# SPE_router_e-fuse_5A.net
KiCad netlist of a schematic drawn in Altium Designer
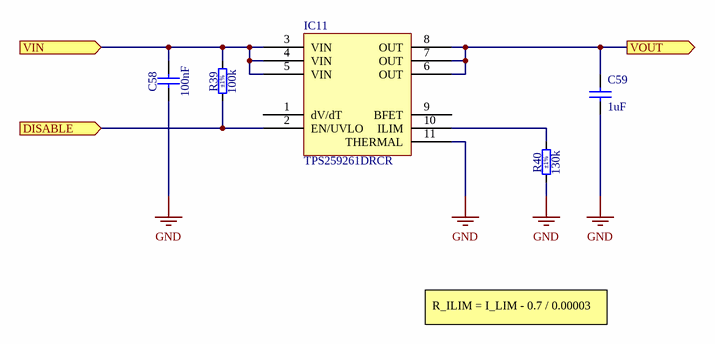
[diagram p0: SPE_router_e-fuse_5A.SchDoc]

(export (version "E")
  (design (tool "Eeschema 10.0.6"))
  (components
    (comp (ref "C58")
      (value "100nF")
      (footprint "CAPC1005X55N")
      (description "Non-polarised capacitor")
      (fields
        (field (name "PART NUMBER") "CC0402_100NF_16V_10%_X7R")
        (field (name "VOLTAGE") "16V")
        (field (name "AUTHOR") "CERN DEM JLC")
      )
      (libsource (lib "Capacitors") (part "Capacitor - non polarized"))
    )
    (comp (ref "C59")
      (value "1uF")
      (footprint "CAPC1005X55N")
      (description "Non-polarised capacitor")
      (fields
        (field (name "PART NUMBER") "CC0402_1UF_16V_10%_X5R")
        (field (name "VOLTAGE") "16V")
        (field (name "AUTHOR") "CERN DEM JLC")
      )
      (libsource (lib "Capacitors") (part "Capacitor - non polarized"))
    )
    (comp (ref "IC11")
      (value "TPS259261DRCR")
      (footprint "VSON50P300X100_HS-11N")
      (description "Hot Swap Controller 13.8V Positive Voltage 10-Pin VSON EP T/R")
      (fields (field (name "MANUFACTURER") "Texas Instruments"))
      (libsource (lib "SPE_router_lib") (part "TPS259261DRCR"))
    )
    (comp (ref "R39")
      (value "100k")
      (footprint "RESC1005X40N")
      (description "Resistor - 1%")
      (fields
        (field (name "TOLERANCE") "±1%")
        (field (name "PART NUMBER") "R0402_100K_1%_0.0625W_100PPM")
        (field (name "POWER") "0.0625W")
        (field (name "AUTHOR") "CERN DEM JLC")
      )
      (libsource (lib "Resistors") (part "Resistor - 1%"))
    )
    (comp (ref "R40")
      (value "130k")
      (footprint "RESC1005X40N")
      (description "Resistor - 1%")
      (fields
        (field (name "TOLERANCE") "±1%")
        (field (name "PART NUMBER") "R0402_130K_1%_0.0625W_100PPM")
        (field (name "POWER") "0.0625W")
        (field (name "AUTHOR") "CERN DEM JLC")
      )
      (libsource (lib "Resistors") (part "Resistor - 1%"))
    )
  )
  (nets
    (net (code "1") (name "/DISABLE") (class "Default")
      (node (ref "IC11") (pin "2") (pinfunction "EN/UVLO_2") (pintype "passive"))
      (node (ref "R39") (pin "1") (pinfunction "1_1") (pintype "passive"))
    )
    (net (code "2") (name "/VIN") (class "Default")
      (node (ref "C58") (pin "2") (pinfunction "2_2") (pintype "passive"))
      (node (ref "IC11") (pin "3") (pinfunction "VIN_3") (pintype "passive"))
      (node (ref "IC11") (pin "4") (pinfunction "VIN_4") (pintype "passive"))
      (node (ref "IC11") (pin "5") (pinfunction "VIN_5") (pintype "passive"))
      (node (ref "R39") (pin "2") (pinfunction "2_2") (pintype "passive"))
    )
    (net (code "3") (name "/VOUT") (class "Default")
      (node (ref "C59") (pin "2") (pinfunction "2_2") (pintype "passive"))
      (node (ref "IC11") (pin "6") (pinfunction "OUT_6") (pintype "passive"))
      (node (ref "IC11") (pin "7") (pinfunction "OUT_7") (pintype "passive"))
      (node (ref "IC11") (pin "8") (pinfunction "OUT_8") (pintype "passive"))
    )
    (net (code "4") (name "GND") (class "Default")
      (node (ref "C58") (pin "1") (pinfunction "1_1") (pintype "passive"))
      (node (ref "C59") (pin "1") (pinfunction "1_1") (pintype "passive"))
      (node (ref "IC11") (pin "11") (pinfunction "THERMAL_11") (pintype "passive"))
      (node (ref "R40") (pin "1") (pinfunction "1_1") (pintype "passive"))
    )
    (net (code "5") (name "Net-(IC11-ILIM)") (class "Default")
      (node (ref "IC11") (pin "10") (pinfunction "ILIM_10") (pintype "passive"))
      (node (ref "R40") (pin "2") (pinfunction "2_2") (pintype "passive"))
    )
    (net (code "6") (name "unconnected-(IC11-BFET-Pad9)") (class "Default")
      (node (ref "IC11") (pin "9") (pinfunction "BFET_9") (pintype "passive"))
    )
    (net (code "7") (name "unconnected-(IC11-dV{slash}dT-Pad1)") (class "Default")
      (node (ref "IC11") (pin "1") (pinfunction "dV/dT_1") (pintype "passive"))
    )
  )
)
